# Conectors_IsolatedSupply.net
KiCad netlist of a schematic drawn in Altium Designer
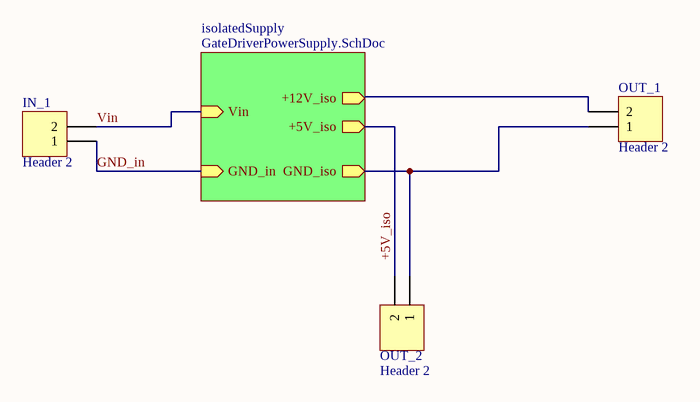
[diagram p0: Conectors_IsolatedSupply.SchDoc]

(export (version "E")
  (design (tool "Eeschema 10.0.6"))
  (components
    (comp (ref "IN_1")
      (value "Header 2")
      (footprint "Header2")
      (description "Header, 2-Pin")
      (libsource (lib "Miscellaneous Connectors") (part "Header 2"))
    )
    (comp (ref "OUT_1")
      (value "Header 2")
      (footprint "Header2")
      (description "Header, 2-Pin")
      (libsource (lib "") (part "Header 2_1"))
    )
    (comp (ref "OUT_2")
      (value "Header 2")
      (footprint "Header2")
      (description "Header, 2-Pin")
      (libsource (lib "") (part "Header 2_2"))
    )
  )
  (nets
    (net (code "1") (name "/+5V_iso") (class "Default")
      (node (ref "OUT_2") (pin "2") (pinfunction "2_2") (pintype "passive"))
    )
    (net (code "3") (name "/GND_in") (class "Default")
      (node (ref "IN_1") (pin "1") (pinfunction "1_1") (pintype "passive"))
    )
    (net (code "4") (name "/GND_iso") (class "Default")
      (node (ref "OUT_1") (pin "1") (pinfunction "1_1") (pintype "passive"))
      (node (ref "OUT_2") (pin "1") (pinfunction "1_1") (pintype "passive"))
    )
    (net (code "5") (name "/Vin") (class "Default")
      (node (ref "IN_1") (pin "2") (pinfunction "2_2") (pintype "passive"))
    )
    (net (code "6") (name "unconnected-(OUT_1-Pad2)") (class "Default")
      (node (ref "OUT_1") (pin "2") (pinfunction "2_2") (pintype "passive"))
    )
  )
)
